# Debug_Board.net
KiCad netlist of a schematic drawn in Altium Designer
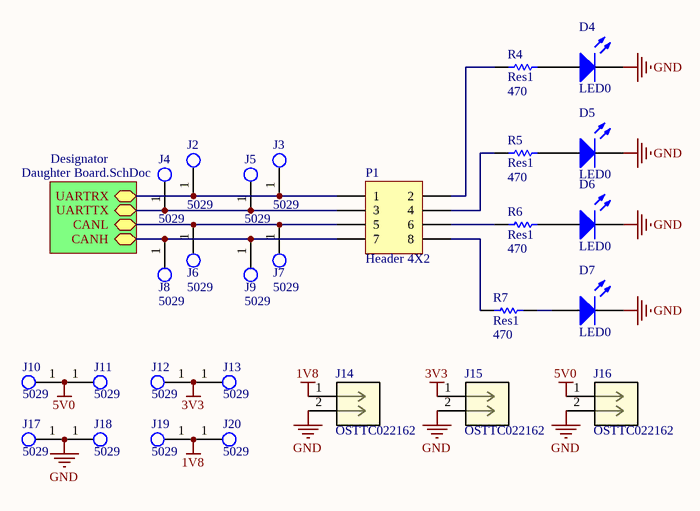
[diagram p0: Debug Board.SchDoc]

(export (version "E")
  (design (tool "Eeschema 10.0.6"))
  (components
    (comp (ref "D4")
      (value "LED0")
      (footprint "1608[0603]")
      (fields (field (name "PUBLISHER") "Altium Limited"))
      (libsource (lib "Miscellaneous Devices") (part "LED0"))
    )
    (comp (ref "D5")
      (value "LED0")
      (footprint "1608[0603]")
      (fields (field (name "PUBLISHER") "Altium Limited"))
      (libsource (lib "Miscellaneous Devices") (part "LED0"))
    )
    (comp (ref "D6")
      (value "LED0")
      (footprint "1608[0603]")
      (fields (field (name "PUBLISHER") "Altium Limited"))
      (libsource (lib "Miscellaneous Devices") (part "LED0"))
    )
    (comp (ref "D7")
      (value "LED0")
      (footprint "1608[0603]")
      (fields (field (name "PUBLISHER") "Altium Limited"))
      (libsource (lib "Miscellaneous Devices") (part "LED0"))
    )
    (comp (ref "J2") (value "5029") (footprint "5029") (libsource (lib "5029") (part "5029")))
    (comp (ref "J3") (value "5029") (footprint "Exposed Pad") (libsource (lib "5029") (part "5029")))
    (comp (ref "J4") (value "5029") (footprint "5029") (libsource (lib "5029") (part "5029")))
    (comp (ref "J5") (value "5029") (footprint "Exposed Pad") (libsource (lib "5029") (part "5029")))
    (comp (ref "J6") (value "5029") (footprint "5029") (libsource (lib "5029") (part "5029")))
    (comp (ref "J7") (value "5029") (footprint "Exposed Pad") (libsource (lib "5029") (part "5029")))
    (comp (ref "J8") (value "5029") (footprint "5029") (libsource (lib "5029") (part "5029")))
    (comp (ref "J9") (value "5029") (footprint "Exposed Pad") (libsource (lib "5029") (part "5029")))
    (comp (ref "J10") (value "5029") (footprint "Exposed Pad") (libsource (lib "5029") (part "5029")))
    (comp (ref "J11") (value "5029") (footprint "5029") (libsource (lib "5029") (part "5029")))
    (comp (ref "J12") (value "5029") (footprint "Exposed Pad") (libsource (lib "5029") (part "5029")))
    (comp (ref "J13") (value "5029") (footprint "5029") (libsource (lib "5029") (part "5029")))
    (comp (ref "J14")
      (value "OSTTC022162")
      (footprint "CONN_OSTTC022162_OST")
      (description "No Description Available")
      (fields (field (name "COPYRIGHT") "Copyright (C) 2018 Accelerated Designs. All rights reserved"))
      (libsource (lib "OSTTC022162") (part "OSTTC022162"))
    )
    (comp (ref "J15")
      (value "OSTTC022162")
      (footprint "CONN_OSTTC022162_OST")
      (description "No Description Available")
      (fields (field (name "COPYRIGHT") "Copyright (C) 2018 Accelerated Designs. All rights reserved"))
      (libsource (lib "OSTTC022162") (part "OSTTC022162"))
    )
    (comp (ref "J16")
      (value "OSTTC022162")
      (footprint "CONN_OSTTC022162_OST")
      (description "No Description Available")
      (fields (field (name "COPYRIGHT") "Copyright (C) 2018 Accelerated Designs. All rights reserved"))
      (libsource (lib "OSTTC022162") (part "OSTTC022162"))
    )
    (comp (ref "J17") (value "5029") (footprint "Exposed Pad") (libsource (lib "5029") (part "5029")))
    (comp (ref "J18") (value "5029") (footprint "5029") (libsource (lib "5029") (part "5029")))
    (comp (ref "J19") (value "5029") (footprint "Exposed Pad") (libsource (lib "5029") (part "5029")))
    (comp (ref "J20") (value "5029") (footprint "5029") (libsource (lib "5029") (part "5029")))
    (comp (ref "P1")
      (value "Header 4X2")
      (footprint "HDR2X4")
      (description "Header, 4-Pin, Dual row")
      (fields (field (name "PUBLISHER") "Altium Limited"))
      (libsource (lib "Miscellaneous Connectors") (part "Header 4X2"))
    )
    (comp (ref "R4")
      (value "Res1")
      (footprint "1608[0603]")
      (description "Resistor")
      (fields (field (name "ALTIUM_VALUE") "470") (field (name "PUBLISHER") "Altium Limited"))
      (libsource (lib "Miscellaneous Devices") (part "Res1"))
    )
    (comp (ref "R5")
      (value "Res1")
      (footprint "1608[0603]")
      (description "Resistor")
      (fields (field (name "ALTIUM_VALUE") "470") (field (name "PUBLISHER") "Altium Limited"))
      (libsource (lib "Miscellaneous Devices") (part "Res1"))
    )
    (comp (ref "R6")
      (value "Res1")
      (footprint "1608[0603]")
      (description "Resistor")
      (fields (field (name "ALTIUM_VALUE") "470") (field (name "PUBLISHER") "Altium Limited"))
      (libsource (lib "Miscellaneous Devices") (part "Res1"))
    )
    (comp (ref "R7")
      (value "Res1")
      (footprint "1608[0603]")
      (description "Resistor")
      (fields (field (name "ALTIUM_VALUE") "470") (field (name "PUBLISHER") "Altium Limited"))
      (libsource (lib "Miscellaneous Devices") (part "Res1"))
    )
  )
  (nets
    (net (code "1") (name "/CANH") (class "Default")
      (node (ref "J8") (pin "1") (pintype "passive"))
      (node (ref "J9") (pin "1") (pintype "passive"))
      (node (ref "P1") (pin "7") (pinfunction "7_7") (pintype "passive"))
    )
    (net (code "2") (name "/CANL") (class "Default")
      (node (ref "J6") (pin "1") (pintype "passive"))
      (node (ref "J7") (pin "1") (pintype "passive"))
      (node (ref "P1") (pin "5") (pinfunction "5_5") (pintype "passive"))
    )
    (net (code "3") (name "/UARTRX") (class "Default")
      (node (ref "J2") (pin "1") (pintype "passive"))
      (node (ref "J3") (pin "1") (pintype "passive"))
      (node (ref "P1") (pin "1") (pinfunction "1_1") (pintype "passive"))
    )
    (net (code "4") (name "/UARTTX") (class "Default")
      (node (ref "J4") (pin "1") (pintype "passive"))
      (node (ref "J5") (pin "1") (pintype "passive"))
      (node (ref "P1") (pin "3") (pinfunction "3_3") (pintype "passive"))
    )
    (net (code "5") (name "1V8") (class "Default")
      (node (ref "J14") (pin "1") (pinfunction "1_1") (pintype "passive"))
      (node (ref "J19") (pin "1") (pintype "passive"))
      (node (ref "J20") (pin "1") (pintype "passive"))
    )
    (net (code "6") (name "3V3") (class "Default")
      (node (ref "J12") (pin "1") (pintype "passive"))
      (node (ref "J13") (pin "1") (pintype "passive"))
      (node (ref "J15") (pin "1") (pinfunction "1_1") (pintype "passive"))
    )
    (net (code "7") (name "5V0") (class "Default")
      (node (ref "J10") (pin "1") (pintype "passive"))
      (node (ref "J11") (pin "1") (pintype "passive"))
      (node (ref "J16") (pin "1") (pinfunction "1_1") (pintype "passive"))
    )
    (net (code "8") (name "GND") (class "Default")
      (node (ref "D4") (pin "2") (pinfunction "K_2") (pintype "passive"))
      (node (ref "D5") (pin "2") (pinfunction "K_2") (pintype "passive"))
      (node (ref "D6") (pin "2") (pinfunction "K_2") (pintype "passive"))
      (node (ref "D7") (pin "2") (pinfunction "K_2") (pintype "passive"))
      (node (ref "J14") (pin "2") (pinfunction "2_2") (pintype "passive"))
      (node (ref "J15") (pin "2") (pinfunction "2_2") (pintype "passive"))
      (node (ref "J16") (pin "2") (pinfunction "2_2") (pintype "passive"))
      (node (ref "J17") (pin "1") (pintype "passive"))
      (node (ref "J18") (pin "1") (pintype "passive"))
    )
    (net (code "9") (name "Net-(D4-A)") (class "Default")
      (node (ref "D4") (pin "1") (pinfunction "A_1") (pintype "passive"))
      (node (ref "R4") (pin "1") (pinfunction "1_1") (pintype "passive"))
    )
    (net (code "10") (name "Net-(D5-A)") (class "Default")
      (node (ref "D5") (pin "1") (pinfunction "A_1") (pintype "passive"))
      (node (ref "R5") (pin "1") (pinfunction "1_1") (pintype "passive"))
    )
    (net (code "11") (name "Net-(D6-A)") (class "Default")
      (node (ref "D6") (pin "1") (pinfunction "A_1") (pintype "passive"))
      (node (ref "R6") (pin "1") (pinfunction "1_1") (pintype "passive"))
    )
    (net (code "12") (name "Net-(D7-A)") (class "Default")
      (node (ref "D7") (pin "1") (pinfunction "A_1") (pintype "passive"))
      (node (ref "R7") (pin "1") (pinfunction "1_1") (pintype "passive"))
    )
    (net (code "13") (name "Net-(P1-Pad2)") (class "Default")
      (node (ref "P1") (pin "2") (pinfunction "2_2") (pintype "passive"))
      (node (ref "R4") (pin "2") (pinfunction "2_2") (pintype "passive"))
    )
    (net (code "14") (name "Net-(P1-Pad4)") (class "Default")
      (node (ref "P1") (pin "4") (pinfunction "4_4") (pintype "passive"))
      (node (ref "R5") (pin "2") (pinfunction "2_2") (pintype "passive"))
    )
    (net (code "15") (name "Net-(P1-Pad6)") (class "Default")
      (node (ref "P1") (pin "6") (pinfunction "6_6") (pintype "passive"))
      (node (ref "R6") (pin "2") (pinfunction "2_2") (pintype "passive"))
    )
    (net (code "16") (name "Net-(P1-Pad8)") (class "Default")
      (node (ref "P1") (pin "8") (pinfunction "8_8") (pintype "passive"))
      (node (ref "R7") (pin "2") (pinfunction "2_2") (pintype "passive"))
    )
  )
)
